# BLOCK2.net
KiCad netlist of a schematic drawn in Altium Designer
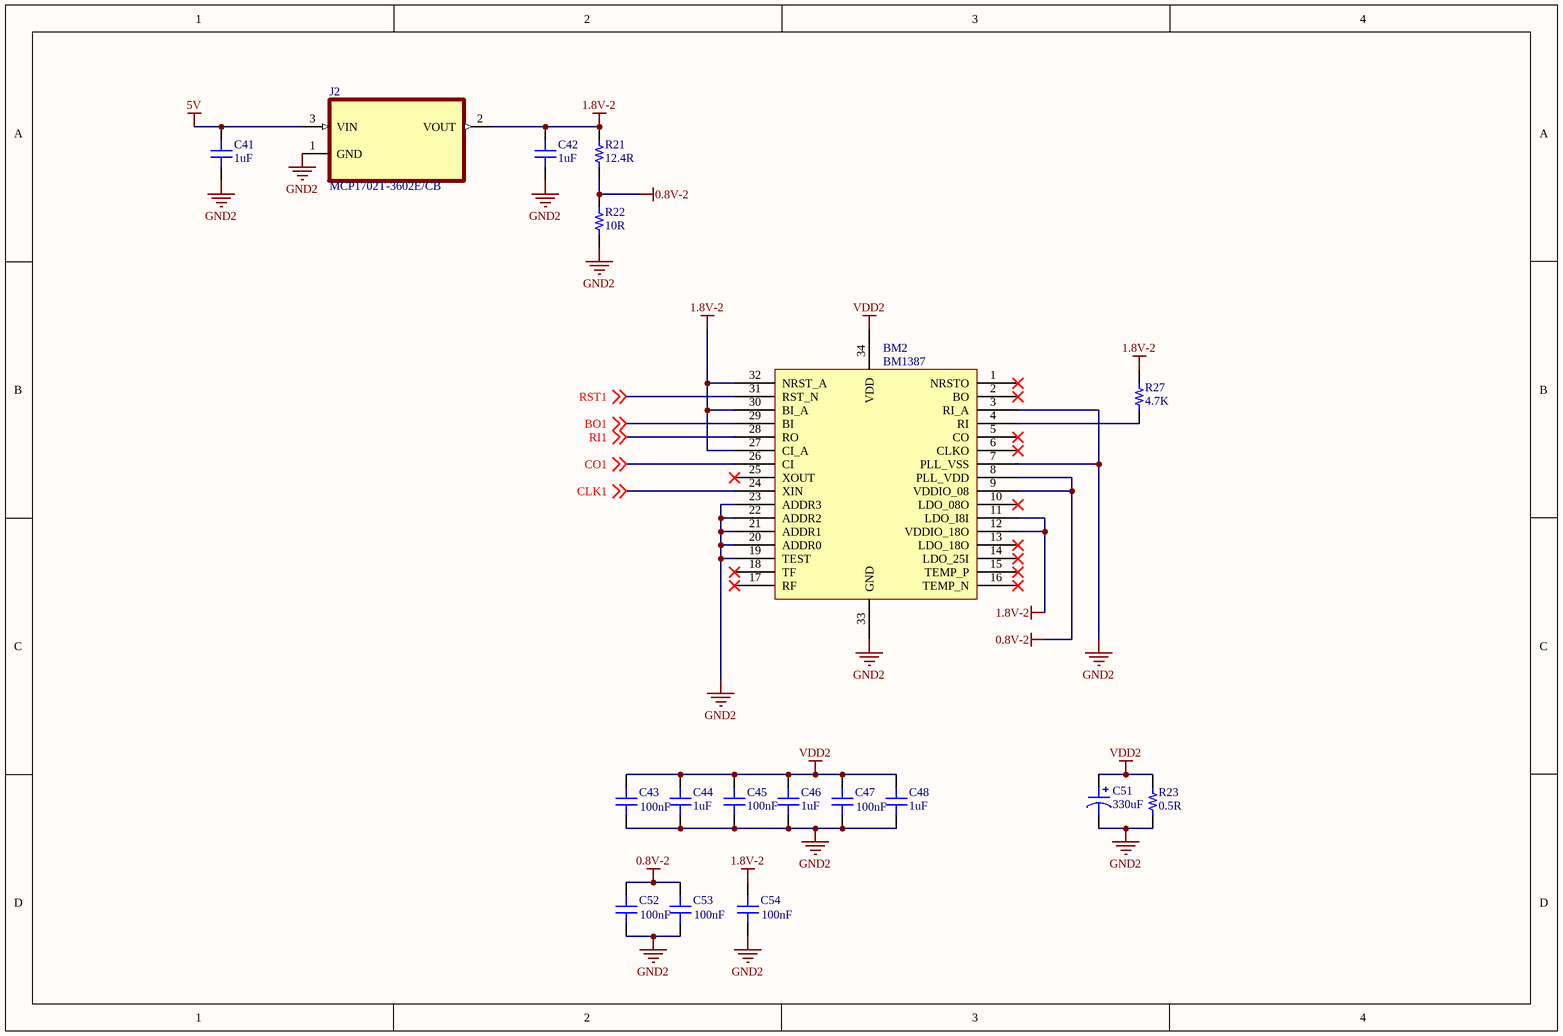
[diagram p0: BLOCK2.SchDoc]

(export (version "E")
  (design (tool "Eeschema 10.0.6"))
  (components
    (comp (ref "BM2") (value "BM1387") (footprint "BM1387") (libsource (lib "USB_MINER") (part "BM1387")))
    (comp (ref "C41") (value "1uF") (footprint "CAP-SMD-0402") (libsource (lib "USB_MINER") (part "CAP")))
    (comp (ref "C42") (value "1uF") (footprint "CAP-SMD-0402") (libsource (lib "USB_MINER") (part "CAP")))
    (comp (ref "C43") (value "100nF") (footprint "CAP_SMD_1206") (libsource (lib "USB_MINER") (part "CAP")))
    (comp (ref "C44") (value "1uF") (footprint "CAP_SMD_1206") (libsource (lib "USB_MINER") (part "CAP")))
    (comp (ref "C45") (value "100nF") (footprint "CAP_SMD_1206") (libsource (lib "USB_MINER") (part "CAP")))
    (comp (ref "C46") (value "1uF") (footprint "CAP_SMD_1206") (libsource (lib "USB_MINER") (part "CAP")))
    (comp (ref "C47") (value "100nF") (footprint "CAP_SMD_1206") (libsource (lib "USB_MINER") (part "CAP")))
    (comp (ref "C48") (value "1uF") (footprint "CAP_SMD_1206") (libsource (lib "USB_MINER") (part "CAP")))
    (comp (ref "C51")
      (value "330uF")
      (footprint "CAP-TAN-CASE-E")
      (libsource (lib "USB_MINER") (part "POLARIZED CAP"))
    )
    (comp (ref "C52") (value "100nF") (footprint "CAP-SMD-0402") (libsource (lib "USB_MINER") (part "CAP")))
    (comp (ref "C53") (value "100nF") (footprint "CAP-SMD-0402") (libsource (lib "USB_MINER") (part "CAP")))
    (comp (ref "C54") (value "100nF") (footprint "CAP-SMD-0402") (libsource (lib "USB_MINER") (part "CAP")))
    (comp (ref "J2")
      (value "MCP1702T-3602E/CB")
      (footprint "SOT95P255X145-3N")
      (description "250 mA Low Quiescent Current LDO Regulator")
      (libsource (lib "USB_MINER") (part "MCP1702T-3602E/CB"))
    )
    (comp (ref "R21") (value "12.4R") (footprint "RES-SMD-0402") (libsource (lib "USB_MINER") (part "RES")))
    (comp (ref "R22") (value "10R") (footprint "RES-SMD-0402") (libsource (lib "USB_MINER") (part "RES")))
    (comp (ref "R23") (value "0.5R") (footprint "RES-SMD-1206") (libsource (lib "USB_MINER") (part "RES")))
    (comp (ref "R27") (value "4.7K") (footprint "RES-SMD-0402") (libsource (lib "USB_MINER") (part "RES")))
  )
  (nets
    (net (code "1") (name "0.8V-2") (class "Default")
      (node (ref "BM2") (pin "8") (pinfunction "PLL_VDD_8") (pintype "passive"))
      (node (ref "BM2") (pin "9") (pinfunction "VDDIO_08_9") (pintype "passive"))
      (node (ref "C52") (pin "2") (pinfunction "2_2") (pintype "passive"))
      (node (ref "C53") (pin "2") (pinfunction "2_2") (pintype "passive"))
      (node (ref "R21") (pin "1") (pinfunction "1_1") (pintype "passive"))
      (node (ref "R22") (pin "2") (pinfunction "2_2") (pintype "passive"))
    )
    (net (code "2") (name "1.8V-2") (class "Default")
      (node (ref "BM2") (pin "11") (pinfunction "LDO_I8I_11") (pintype "passive"))
      (node (ref "BM2") (pin "12") (pinfunction "VDDIO_18O_12") (pintype "passive"))
      (node (ref "BM2") (pin "27") (pinfunction "CI_A_27") (pintype "passive"))
      (node (ref "BM2") (pin "30") (pinfunction "BI_A_30") (pintype "passive"))
      (node (ref "BM2") (pin "32") (pinfunction "NRST_A_32") (pintype "passive"))
      (node (ref "C42") (pin "2") (pinfunction "2_2") (pintype "passive"))
      (node (ref "C54") (pin "2") (pinfunction "2_2") (pintype "passive"))
      (node (ref "J2") (pin "2") (pinfunction "VOUT_2") (pintype "output"))
      (node (ref "R21") (pin "2") (pinfunction "2_2") (pintype "passive"))
      (node (ref "R27") (pin "2") (pinfunction "2_2") (pintype "passive"))
    )
    (net (code "3") (name "5V") (class "Default")
      (node (ref "C41") (pin "2") (pinfunction "2_2") (pintype "passive"))
      (node (ref "J2") (pin "3") (pinfunction "VIN_3") (pintype "input"))
    )
    (net (code "4") (name "BO1") (class "Default")
      (node (ref "BM2") (pin "29") (pinfunction "BI_29") (pintype "passive"))
    )
    (net (code "5") (name "CLK1") (class "Default")
      (node (ref "BM2") (pin "24") (pinfunction "XIN_24") (pintype "passive"))
    )
    (net (code "6") (name "CO1") (class "Default")
      (node (ref "BM2") (pin "26") (pinfunction "CI_26") (pintype "passive"))
    )
    (net (code "7") (name "GND2") (class "Default")
      (node (ref "BM2") (pin "19") (pinfunction "TEST_19") (pintype "passive"))
      (node (ref "BM2") (pin "20") (pinfunction "ADDR0_20") (pintype "passive"))
      (node (ref "BM2") (pin "21") (pinfunction "ADDR1_21") (pintype "passive"))
      (node (ref "BM2") (pin "22") (pinfunction "ADDR2_22") (pintype "passive"))
      (node (ref "BM2") (pin "23") (pinfunction "ADDR3_23") (pintype "passive"))
      (node (ref "BM2") (pin "3") (pinfunction "RI_A_3") (pintype "passive"))
      (node (ref "BM2") (pin "33") (pinfunction "GND_33") (pintype "passive"))
      (node (ref "BM2") (pin "7") (pinfunction "PLL_VSS_7") (pintype "passive"))
      (node (ref "C41") (pin "1") (pinfunction "1_1") (pintype "passive"))
      (node (ref "C42") (pin "1") (pinfunction "1_1") (pintype "passive"))
      (node (ref "C43") (pin "1") (pinfunction "1_1") (pintype "passive"))
      (node (ref "C44") (pin "1") (pinfunction "1_1") (pintype "passive"))
      (node (ref "C45") (pin "1") (pinfunction "1_1") (pintype "passive"))
      (node (ref "C46") (pin "1") (pinfunction "1_1") (pintype "passive"))
      (node (ref "C47") (pin "1") (pinfunction "1_1") (pintype "passive"))
      (node (ref "C48") (pin "1") (pinfunction "1_1") (pintype "passive"))
      (node (ref "C51") (pin "2") (pinfunction "2_2") (pintype "passive"))
      (node (ref "C52") (pin "1") (pinfunction "1_1") (pintype "passive"))
      (node (ref "C53") (pin "1") (pinfunction "1_1") (pintype "passive"))
      (node (ref "C54") (pin "1") (pinfunction "1_1") (pintype "passive"))
      (node (ref "J2") (pin "1") (pinfunction "GND_1") (pintype "passive"))
      (node (ref "R22") (pin "1") (pinfunction "1_1") (pintype "passive"))
      (node (ref "R23") (pin "1") (pinfunction "1_1") (pintype "passive"))
    )
    (net (code "8") (name "Net-(BM2-RI)") (class "Default")
      (node (ref "BM2") (pin "4") (pinfunction "RI_4") (pintype "passive"))
      (node (ref "R27") (pin "1") (pinfunction "1_1") (pintype "passive"))
    )
    (net (code "9") (name "RI1") (class "Default")
      (node (ref "BM2") (pin "28") (pinfunction "RO_28") (pintype "passive"))
    )
    (net (code "10") (name "RST1") (class "Default")
      (node (ref "BM2") (pin "31") (pinfunction "RST_N_31") (pintype "passive"))
    )
    (net (code "11") (name "VDD2") (class "Default")
      (node (ref "BM2") (pin "34") (pinfunction "VDD_34") (pintype "passive"))
      (node (ref "C43") (pin "2") (pinfunction "2_2") (pintype "passive"))
      (node (ref "C44") (pin "2") (pinfunction "2_2") (pintype "passive"))
      (node (ref "C45") (pin "2") (pinfunction "2_2") (pintype "passive"))
      (node (ref "C46") (pin "2") (pinfunction "2_2") (pintype "passive"))
      (node (ref "C47") (pin "2") (pinfunction "2_2") (pintype "passive"))
      (node (ref "C48") (pin "2") (pinfunction "2_2") (pintype "passive"))
      (node (ref "C51") (pin "1") (pinfunction "1_1") (pintype "passive"))
      (node (ref "R23") (pin "2") (pinfunction "2_2") (pintype "passive"))
    )
    (net (code "12") (name "unconnected-(BM2-BO-Pad2)") (class "Default")
      (node (ref "BM2") (pin "2") (pinfunction "BO_2") (pintype "passive+no_connect"))
    )
    (net (code "13") (name "unconnected-(BM2-CLKO-Pad6)") (class "Default")
      (node (ref "BM2") (pin "6") (pinfunction "CLKO_6") (pintype "passive+no_connect"))
    )
    (net (code "14") (name "unconnected-(BM2-CO-Pad5)") (class "Default")
      (node (ref "BM2") (pin "5") (pinfunction "CO_5") (pintype "passive+no_connect"))
    )
    (net (code "15") (name "unconnected-(BM2-LDO_08O-Pad10)") (class "Default")
      (node (ref "BM2") (pin "10") (pinfunction "LDO_08O_10") (pintype "passive+no_connect"))
    )
    (net (code "16") (name "unconnected-(BM2-LDO_18O-Pad13)") (class "Default")
      (node (ref "BM2") (pin "13") (pinfunction "LDO_18O_13") (pintype "passive+no_connect"))
    )
    (net (code "17") (name "unconnected-(BM2-LDO_25I-Pad14)") (class "Default")
      (node (ref "BM2") (pin "14") (pinfunction "LDO_25I_14") (pintype "passive+no_connect"))
    )
    (net (code "18") (name "unconnected-(BM2-NRSTO-Pad1)") (class "Default")
      (node (ref "BM2") (pin "1") (pinfunction "NRSTO_1") (pintype "passive+no_connect"))
    )
    (net (code "19") (name "unconnected-(BM2-RF-Pad17)") (class "Default")
      (node (ref "BM2") (pin "17") (pinfunction "RF_17") (pintype "passive+no_connect"))
    )
    (net (code "20") (name "unconnected-(BM2-TEMP_N-Pad16)") (class "Default")
      (node (ref "BM2") (pin "16") (pinfunction "TEMP_N_16") (pintype "passive+no_connect"))
    )
    (net (code "21") (name "unconnected-(BM2-TEMP_P-Pad15)") (class "Default")
      (node (ref "BM2") (pin "15") (pinfunction "TEMP_P_15") (pintype "passive+no_connect"))
    )
    (net (code "22") (name "unconnected-(BM2-TF-Pad18)") (class "Default")
      (node (ref "BM2") (pin "18") (pinfunction "TF_18") (pintype "passive+no_connect"))
    )
    (net (code "23") (name "unconnected-(BM2-XOUT-Pad25)") (class "Default")
      (node (ref "BM2") (pin "25") (pinfunction "XOUT_25") (pintype "passive+no_connect"))
    )
  )
)
